# Polarshield_v2_1.net
KiCad netlist of a schematic drawn in EAGLE
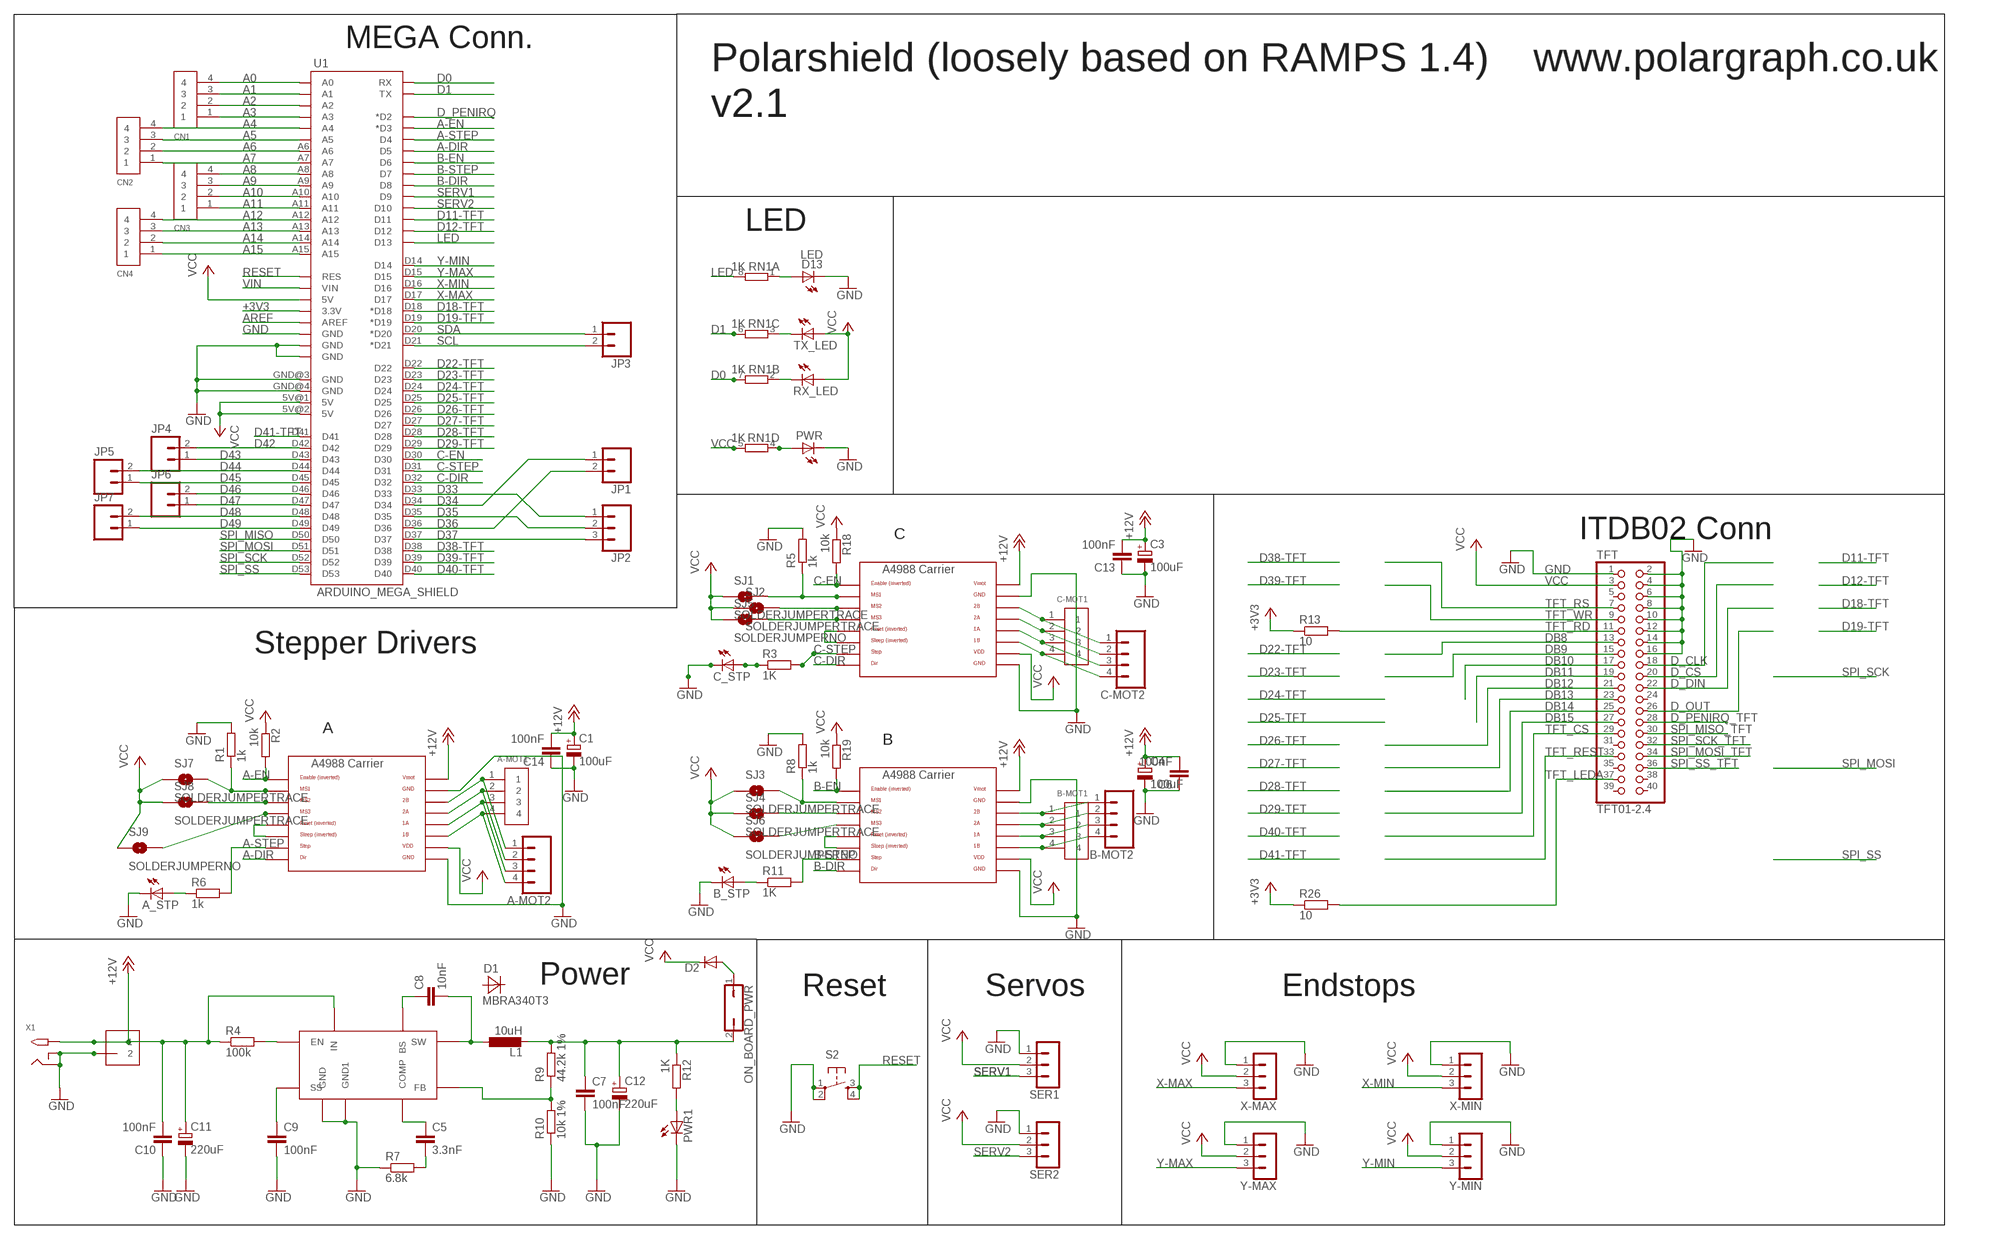
[diagram p0: schematic, sheet 1, part 1 of 2]
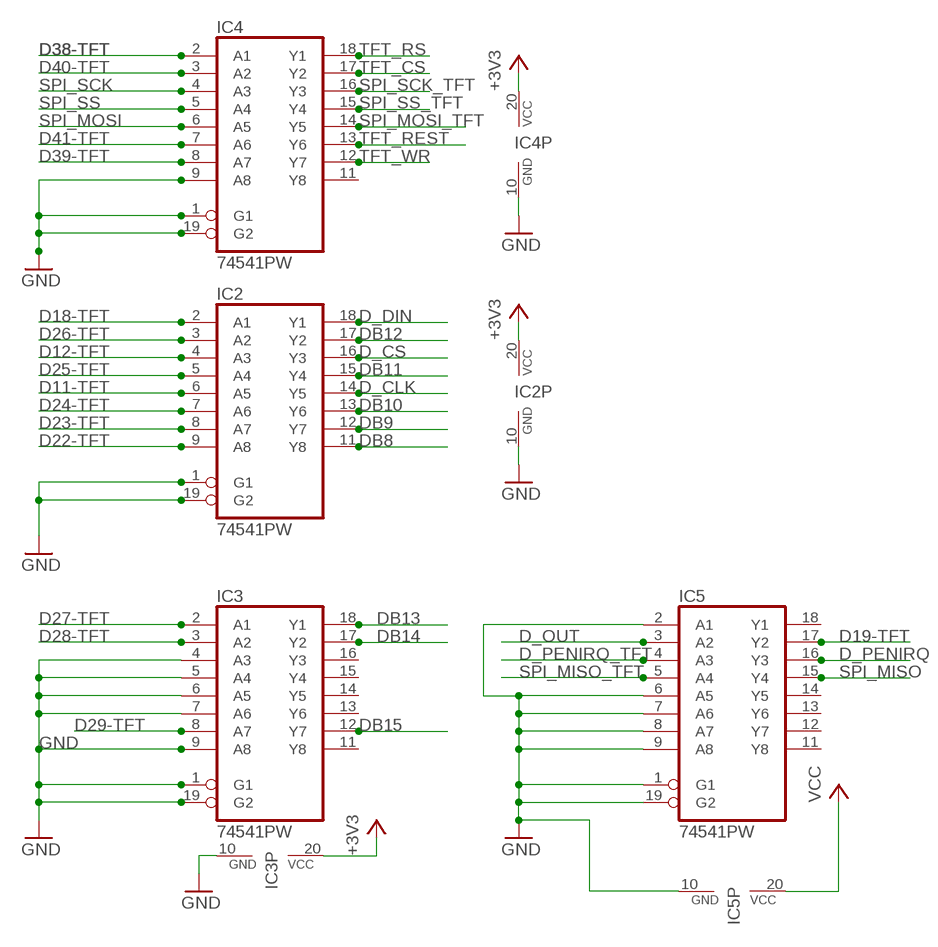
[diagram p1: schematic, sheet 1, part 2 of 2]

(export (version "E")
  (design (tool "Eeschema 10.0.6"))
  (components
    (comp (ref "A-MOT1")
      (value "1X4-BIG")
      (footprint "eagle-import:1X04-BIG")
      (libsource (lib "eagle-import") (part "adafruit_1X4-BIG"))
    )
    (comp (ref "A-MOT2")
      (value "M04SCREW")
      (footprint "eagle-import:SCREWTERMINAL-3.5MM-4")
      (libsource (lib "eagle-import") (part "M04SCREW"))
    )
    (comp (ref "A_STP")
      (value "LEDCHIP-LED0805")
      (footprint "eagle-import:CHIP-LED0805")
      (libsource (lib "eagle-import") (part "LEDCHIP-LED0805"))
    )
    (comp (ref "B-MOT1")
      (value "1X4-BIG")
      (footprint "eagle-import:1X04-BIG")
      (libsource (lib "eagle-import") (part "adafruit_1X4-BIG"))
    )
    (comp (ref "B-MOT2")
      (value "M04SCREW")
      (footprint "eagle-import:SCREWTERMINAL-3.5MM-4")
      (libsource (lib "eagle-import") (part "M04SCREW"))
    )
    (comp (ref "B_STP")
      (value "LEDCHIP-LED0805")
      (footprint "eagle-import:CHIP-LED0805")
      (libsource (lib "eagle-import") (part "LEDCHIP-LED0805"))
    )
    (comp (ref "C-MOT1")
      (value "1X4-BIG")
      (footprint "eagle-import:1X04-BIG")
      (libsource (lib "eagle-import") (part "adafruit_1X4-BIG"))
    )
    (comp (ref "C-MOT2")
      (value "M04SCREW")
      (footprint "eagle-import:SCREWTERMINAL-3.5MM-4")
      (libsource (lib "eagle-import") (part "M04SCREW"))
    )
    (comp (ref "C1")
      (value "100uF")
      (footprint "eagle-import:153CLV-0605")
      (libsource (lib "eagle-import") (part "CPOL-EU153CLV-0605"))
    )
    (comp (ref "C3")
      (value "100uF")
      (footprint "eagle-import:153CLV-0605")
      (libsource (lib "eagle-import") (part "CPOL-EU153CLV-0605"))
    )
    (comp (ref "C4")
      (value "100uF")
      (footprint "eagle-import:153CLV-0605")
      (libsource (lib "eagle-import") (part "CPOL-EU153CLV-0605"))
    )
    (comp (ref "C5")
      (value "3.3nF")
      (footprint "eagle-import:C0805K")
      (libsource (lib "eagle-import") (part "C-EUC0805K"))
    )
    (comp (ref "C6")
      (value "100nF")
      (footprint "eagle-import:C0805")
      (libsource (lib "eagle-import") (part "C-EUC0805"))
    )
    (comp (ref "C7")
      (value "100nF")
      (footprint "eagle-import:C0805K")
      (libsource (lib "eagle-import") (part "C-EUC0805K"))
    )
    (comp (ref "C8")
      (value "10nF")
      (footprint "eagle-import:C0805K")
      (libsource (lib "eagle-import") (part "C-EUC0805K"))
    )
    (comp (ref "C9")
      (value "100nF")
      (footprint "eagle-import:C0805K")
      (libsource (lib "eagle-import") (part "C-EUC0805K"))
    )
    (comp (ref "C10")
      (value "100nF")
      (footprint "eagle-import:C0805K")
      (libsource (lib "eagle-import") (part "C-EUC0805K"))
    )
    (comp (ref "C11")
      (value "220uF")
      (footprint "eagle-import:153CLV-0807")
      (libsource (lib "eagle-import") (part "resistor_CPOL-EU153CLV-0807"))
    )
    (comp (ref "C12")
      (value "220uF")
      (footprint "eagle-import:153CLV-0807")
      (libsource (lib "eagle-import") (part "resistor_CPOL-EU153CLV-0807"))
    )
    (comp (ref "C13")
      (value "100nF")
      (footprint "eagle-import:C0805")
      (libsource (lib "eagle-import") (part "C-EUC0805"))
    )
    (comp (ref "C14")
      (value "100nF")
      (footprint "eagle-import:C0805")
      (libsource (lib "eagle-import") (part "C-EUC0805"))
    )
    (comp (ref "CN1")
      (value "1X4-CLEANBIG")
      (footprint "eagle-import:1X04-CLEANBIG")
      (libsource (lib "eagle-import") (part "1X4-CLEANBIG"))
    )
    (comp (ref "CN2")
      (value "1X4-CLEANBIG")
      (footprint "eagle-import:1X04-CLEANBIG")
      (libsource (lib "eagle-import") (part "1X4-CLEANBIG"))
    )
    (comp (ref "CN3")
      (value "1X4-CLEANBIG")
      (footprint "eagle-import:1X04-CLEANBIG")
      (libsource (lib "eagle-import") (part "1X4-CLEANBIG"))
    )
    (comp (ref "CN4")
      (value "1X4-CLEANBIG")
      (footprint "eagle-import:1X04-CLEANBIG")
      (libsource (lib "eagle-import") (part "1X4-CLEANBIG"))
    )
    (comp (ref "C_STP")
      (value "LEDCHIP-LED0805")
      (footprint "eagle-import:CHIP-LED0805")
      (libsource (lib "eagle-import") (part "LEDCHIP-LED0805"))
    )
    (comp (ref "D1")
      (value "MBRA340T3")
      (footprint "eagle-import:SMA")
      (libsource (lib "eagle-import") (part "MBRA340T3"))
    )
    (comp (ref "D2")
      (value "DIODE-DO214BA")
      (footprint "eagle-import:DO214BA")
      (libsource (lib "eagle-import") (part "DIODE-DO214BA"))
    )
    (comp (ref "D13")
      (value "LED")
      (footprint "eagle-import:CHIP-LED0805")
      (libsource (lib "eagle-import") (part "LEDCHIP-LED0805"))
    )
    (comp (ref "IC1")
      (value "MP2307")
      (footprint "eagle-import:SOIC8")
      (libsource (lib "eagle-import") (part "MP2307"))
    )
    (comp (ref "IC2")
      (value "74541PW")
      (footprint "eagle-import:TSSOP20")
      (libsource (lib "eagle-import") (part "74541PW"))
    )
    (comp (ref "IC3")
      (value "74541PW")
      (footprint "eagle-import:TSSOP20")
      (libsource (lib "eagle-import") (part "74541PW"))
    )
    (comp (ref "IC4")
      (value "74541PW")
      (footprint "eagle-import:TSSOP20")
      (libsource (lib "eagle-import") (part "74541PW"))
    )
    (comp (ref "IC5")
      (value "74541PW")
      (footprint "eagle-import:TSSOP20")
      (libsource (lib "eagle-import") (part "74541PW"))
    )
    (comp (ref "J1")
      (value "1X2-3.5MM")
      (footprint "eagle-import:1X2-3.5MM")
      (libsource (lib "eagle-import") (part "1X2-3.5MM"))
    )
    (comp (ref "JP1")
      (value "M02POGO_PIN_HOLES_ONLY")
      (footprint "eagle-import:1X02_PP_HOLES_ONLY")
      (libsource (lib "eagle-import") (part "M02POGO_PIN_HOLES_ONLY"))
    )
    (comp (ref "JP2")
      (value "M03POGO_PIN_HOLES_ONLY")
      (footprint "eagle-import:1X03_PP_HOLES_ONLY")
      (libsource (lib "eagle-import") (part "M03POGO_PIN_HOLES_ONLY"))
    )
    (comp (ref "JP3")
      (value "M02POGO_PIN_HOLES_ONLY")
      (footprint "eagle-import:1X02_PP_HOLES_ONLY")
      (libsource (lib "eagle-import") (part "M02POGO_PIN_HOLES_ONLY"))
    )
    (comp (ref "JP4")
      (value "M02POGO_PIN_HOLES_ONLY")
      (footprint "eagle-import:1X02_PP_HOLES_ONLY")
      (libsource (lib "eagle-import") (part "M02POGO_PIN_HOLES_ONLY"))
    )
    (comp (ref "JP5")
      (value "M02POGO_PIN_HOLES_ONLY")
      (footprint "eagle-import:1X02_PP_HOLES_ONLY")
      (libsource (lib "eagle-import") (part "M02POGO_PIN_HOLES_ONLY"))
    )
    (comp (ref "JP6")
      (value "M02POGO_PIN_HOLES_ONLY")
      (footprint "eagle-import:1X02_PP_HOLES_ONLY")
      (libsource (lib "eagle-import") (part "M02POGO_PIN_HOLES_ONLY"))
    )
    (comp (ref "JP7")
      (value "M02POGO_PIN_HOLES_ONLY")
      (footprint "eagle-import:1X02_PP_HOLES_ONLY")
      (libsource (lib "eagle-import") (part "M02POGO_PIN_HOLES_ONLY"))
    )
    (comp (ref "L1")
      (value "10uH")
      (footprint "eagle-import:PIS2816")
      (libsource (lib "eagle-import") (part "L-EUPIS2816"))
    )
    (comp (ref "ON_BOARD_PWR")
      (value "JP1Q")
      (footprint "eagle-import:JP1")
      (libsource (lib "eagle-import") (part "JP1Q"))
    )
    (comp (ref "PWR")
      (value "LEDCHIP-LED0805")
      (footprint "eagle-import:CHIP-LED0805")
      (libsource (lib "eagle-import") (part "LEDCHIP-LED0805"))
    )
    (comp (ref "PWR1")
      (value "LEDCHIP-LED0805")
      (footprint "eagle-import:CHIP-LED0805")
      (libsource (lib "eagle-import") (part "LEDCHIP-LED0805"))
    )
    (comp (ref "R1")
      (value "1k")
      (footprint "eagle-import:R0805")
      (libsource (lib "eagle-import") (part "R-EU_R0805"))
    )
    (comp (ref "R2")
      (value "10k")
      (footprint "eagle-import:R0805")
      (libsource (lib "eagle-import") (part "R-EU_R0805"))
    )
    (comp (ref "R3")
      (value "1K")
      (footprint "eagle-import:R0805")
      (libsource (lib "eagle-import") (part "R-EU_R0805"))
    )
    (comp (ref "R4")
      (value "100k")
      (footprint "eagle-import:R0805")
      (libsource (lib "eagle-import") (part "resistor_R-EU_R0805"))
    )
    (comp (ref "R5")
      (value "1k")
      (footprint "eagle-import:R0805")
      (libsource (lib "eagle-import") (part "R-EU_R0805"))
    )
    (comp (ref "R6")
      (value "1k")
      (footprint "eagle-import:R0805")
      (libsource (lib "eagle-import") (part "R-EU_R0805"))
    )
    (comp (ref "R7")
      (value "6.8k")
      (footprint "eagle-import:R0805")
      (libsource (lib "eagle-import") (part "resistor_R-EU_R0805"))
    )
    (comp (ref "R8")
      (value "1k")
      (footprint "eagle-import:R0805")
      (libsource (lib "eagle-import") (part "R-EU_R0805"))
    )
    (comp (ref "R9")
      (value "44.2k 1%")
      (footprint "eagle-import:R0805")
      (libsource (lib "eagle-import") (part "resistor_R-EU_R0805"))
    )
    (comp (ref "R10")
      (value "10k 1%")
      (footprint "eagle-import:R0805")
      (libsource (lib "eagle-import") (part "resistor_R-EU_R0805"))
    )
    (comp (ref "R11")
      (value "1K")
      (footprint "eagle-import:R0805")
      (libsource (lib "eagle-import") (part "R-EU_R0805"))
    )
    (comp (ref "R12")
      (value "1K")
      (footprint "eagle-import:R0805")
      (libsource (lib "eagle-import") (part "R-EU_R0805"))
    )
    (comp (ref "R13")
      (value "10")
      (footprint "eagle-import:R0805")
      (libsource (lib "eagle-import") (part "resistor_R-EU_R0805"))
    )
    (comp (ref "R18")
      (value "10k")
      (footprint "eagle-import:R0805")
      (libsource (lib "eagle-import") (part "R-EU_R0805"))
    )
    (comp (ref "R19")
      (value "10k")
      (footprint "eagle-import:R0805")
      (libsource (lib "eagle-import") (part "R-EU_R0805"))
    )
    (comp (ref "R26")
      (value "10")
      (footprint "eagle-import:R0805")
      (libsource (lib "eagle-import") (part "resistor_R-EU_R0805"))
    )
    (comp (ref "RN1")
      (value "1K")
      (footprint "eagle-import:EXBS8V")
      (libsource (lib "eagle-import") (part "4R-NEXBS8V"))
    )
    (comp (ref "RX_LED")
      (value "LEDCHIP-LED0805")
      (footprint "eagle-import:CHIP-LED0805")
      (libsource (lib "eagle-import") (part "LEDCHIP-LED0805"))
    )
    (comp (ref "S2")
      (value "TAC_SWITCHPTH")
      (footprint "eagle-import:TACTILE-PTH")
      (libsource (lib "eagle-import") (part "TAC_SWITCHPTH"))
    )
    (comp (ref "SER1")
      (value "3PIN-HEADER")
      (footprint "eagle-import:3PIN-HEADER")
      (libsource (lib "eagle-import") (part "3PIN-HEADER"))
    )
    (comp (ref "SER2")
      (value "3PIN-HEADER")
      (footprint "eagle-import:3PIN-HEADER")
      (libsource (lib "eagle-import") (part "3PIN-HEADER"))
    )
    (comp (ref "SJ1")
      (value "SOLDERJUMPERTRACE")
      (footprint "eagle-import:SJ_2S-TRACE")
      (libsource (lib "eagle-import") (part "SOLDERJUMPERTRACE"))
    )
    (comp (ref "SJ2")
      (value "SOLDERJUMPERTRACE")
      (footprint "eagle-import:SJ_2S-TRACE")
      (libsource (lib "eagle-import") (part "SOLDERJUMPERTRACE"))
    )
    (comp (ref "SJ3")
      (value "SOLDERJUMPERTRACE")
      (footprint "eagle-import:SJ_2S-TRACE")
      (libsource (lib "eagle-import") (part "SOLDERJUMPERTRACE"))
    )
    (comp (ref "SJ4")
      (value "SOLDERJUMPERTRACE")
      (footprint "eagle-import:SJ_2S-TRACE")
      (libsource (lib "eagle-import") (part "SOLDERJUMPERTRACE"))
    )
    (comp (ref "SJ5")
      (value "SOLDERJUMPERNO")
      (footprint "eagle-import:SJ_2S-NO")
      (libsource (lib "eagle-import") (part "SOLDERJUMPERNO"))
    )
    (comp (ref "SJ6")
      (value "SOLDERJUMPERNO")
      (footprint "eagle-import:SJ_2S-NO")
      (libsource (lib "eagle-import") (part "SOLDERJUMPERNO"))
    )
    (comp (ref "SJ7")
      (value "SOLDERJUMPERTRACE")
      (footprint "eagle-import:SJ_2S-TRACE")
      (libsource (lib "eagle-import") (part "SOLDERJUMPERTRACE"))
    )
    (comp (ref "SJ8")
      (value "SOLDERJUMPERTRACE")
      (footprint "eagle-import:SJ_2S-TRACE")
      (libsource (lib "eagle-import") (part "SOLDERJUMPERTRACE"))
    )
    (comp (ref "SJ9")
      (value "SOLDERJUMPERNO")
      (footprint "eagle-import:SJ_2S-NO")
      (libsource (lib "eagle-import") (part "SOLDERJUMPERNO"))
    )
    (comp (ref "TFT")
      (value "TFT01-2.4")
      (footprint "eagle-import:TFT01-2.4")
      (libsource (lib "eagle-import") (part "TFT01-2.4"))
    )
    (comp (ref "TX_LED")
      (value "LEDCHIP-LED0805")
      (footprint "eagle-import:CHIP-LED0805")
      (libsource (lib "eagle-import") (part "LEDCHIP-LED0805"))
    )
    (comp (ref "U$1")
      (value "A4988BREAKOUT")
      (footprint "eagle-import:A4988BREAKOUT")
      (libsource (lib "eagle-import") (part "A4988BREAKOUT"))
    )
    (comp (ref "U$6")
      (value "A4988BREAKOUT")
      (footprint "eagle-import:A4988BREAKOUT")
      (libsource (lib "eagle-import") (part "A4988BREAKOUT"))
    )
    (comp (ref "U$7")
      (value "A4988BREAKOUT")
      (footprint "eagle-import:A4988BREAKOUT")
      (libsource (lib "eagle-import") (part "A4988BREAKOUT"))
    )
    (comp (ref "U1")
      (value "ARDUINO_MEGA_SHIELD")
      (footprint "eagle-import:ARDUINO_MEGA_SHIELD")
      (libsource (lib "eagle-import") (part "ARDUINO_MEGA_SHIELD"))
    )
    (comp (ref "X-MAX")
      (value "3PIN-HEADER")
      (footprint "eagle-import:3PIN-HEADER")
      (libsource (lib "eagle-import") (part "3PIN-HEADER"))
    )
    (comp (ref "X-MIN")
      (value "3PIN-HEADER")
      (footprint "eagle-import:3PIN-HEADER")
      (libsource (lib "eagle-import") (part "3PIN-HEADER"))
    )
    (comp (ref "X1")
      (value "2.1MMJACKTHM")
      (footprint "eagle-import:PJ-102A")
      (libsource (lib "eagle-import") (part "2.1MMJACKTHM"))
    )
    (comp (ref "Y-MAX")
      (value "3PIN-HEADER")
      (footprint "eagle-import:3PIN-HEADER")
      (libsource (lib "eagle-import") (part "3PIN-HEADER"))
    )
    (comp (ref "Y-MIN")
      (value "3PIN-HEADER")
      (footprint "eagle-import:3PIN-HEADER")
      (libsource (lib "eagle-import") (part "3PIN-HEADER"))
    )
  )
  (nets
    (net (code "1") (name "+3V3") (class "Default")
      (node (ref "IC2") (pin "20") (pinfunction "VCC_20") (pintype "power_in"))
      (node (ref "IC3") (pin "20") (pinfunction "VCC_20") (pintype "power_in"))
      (node (ref "IC4") (pin "20") (pinfunction "VCC_20") (pintype "power_in"))
      (node (ref "R13") (pin "1") (pinfunction "1_1") (pintype "passive"))
      (node (ref "R26") (pin "1") (pinfunction "1_1") (pintype "passive"))
      (node (ref "U1") (pin "3.3V") (pinfunction "3.3V_3.3V") (pintype "bidirectional"))
    )
    (net (code "2") (name "+12V") (class "Default")
      (node (ref "C1") (pin "+") (pinfunction "+_+") (pintype "passive"))
      (node (ref "C10") (pin "2") (pinfunction "2_2") (pintype "passive"))
      (node (ref "C11") (pin "+") (pinfunction "+_+") (pintype "passive"))
      (node (ref "C13") (pin "2") (pinfunction "2_2") (pintype "passive"))
      (node (ref "C14") (pin "2") (pinfunction "2_2") (pintype "passive"))
      (node (ref "C3") (pin "+") (pinfunction "+_+") (pintype "passive"))
      (node (ref "C4") (pin "+") (pinfunction "+_+") (pintype "passive"))
      (node (ref "C6") (pin "2") (pinfunction "2_2") (pintype "passive"))
      (node (ref "IC1") (pin "IN") (pinfunction "IN_IN") (pintype "bidirectional"))
      (node (ref "J1") (pin "1") (pinfunction "1_1") (pintype "passive"))
      (node (ref "R4") (pin "1") (pinfunction "1_1") (pintype "passive"))
      (node (ref "U$1") (pin "VMOT") (pinfunction "VMOT_VMOT") (pintype "power_in"))
      (node (ref "U$6") (pin "VMOT") (pinfunction "VMOT_VMOT") (pintype "power_in"))
      (node (ref "U$7") (pin "VMOT") (pinfunction "VMOT_VMOT") (pintype "power_in"))
      (node (ref "X1") (pin "TIP") (pinfunction "TIP_TIP") (pintype "bidirectional"))
    )
    (net (code "3") (name "/A-DIR") (class "Default")
      (node (ref "U$1") (pin "DIR") (pinfunction "DIR_DIR") (pintype "input"))
      (node (ref "U1") (pin "D5") (pinfunction "D5_D5") (pintype "bidirectional"))
    )
    (net (code "4") (name "/A-EN") (class "Default")
      (node (ref "R2") (pin "2") (pinfunction "2_2") (pintype "passive"))
      (node (ref "U$1") (pin "EN") (pinfunction "EN_EN") (pintype "input"))
      (node (ref "U1") (pin "D3") (pinfunction "*D3_D3") (pintype "bidirectional"))
    )
    (net (code "5") (name "/A-STEP") (class "Default")
      (node (ref "R6") (pin "2") (pinfunction "2_2") (pintype "passive"))
      (node (ref "U$1") (pin "STEP") (pinfunction "STEP_STEP") (pintype "input"))
      (node (ref "U1") (pin "D4") (pinfunction "D4_D4") (pintype "bidirectional"))
    )
    (net (code "6") (name "/A0") (class "Default")
      (node (ref "CN1") (pin "4") (pinfunction "4_4") (pintype "bidirectional"))
      (node (ref "U1") (pin "A0") (pinfunction "A0_A0") (pintype "bidirectional"))
    )
    (net (code "7") (name "/A1") (class "Default")
      (node (ref "CN1") (pin "3") (pinfunction "3_3") (pintype "bidirectional"))
      (node (ref "U1") (pin "A1") (pinfunction "A1_A1") (pintype "bidirectional"))
    )
    (net (code "8") (name "/A2") (class "Default")
      (node (ref "CN1") (pin "2") (pinfunction "2_2") (pintype "bidirectional"))
      (node (ref "U1") (pin "A2") (pinfunction "A2_A2") (pintype "bidirectional"))
    )
    (net (code "9") (name "/A3") (class "Default")
      (node (ref "CN1") (pin "1") (pinfunction "1_1") (pintype "bidirectional"))
      (node (ref "U1") (pin "A3") (pinfunction "A3_A3") (pintype "bidirectional"))
    )
    (net (code "10") (name "/A4") (class "Default")
      (node (ref "CN2") (pin "4") (pinfunction "4_4") (pintype "bidirectional"))
      (node (ref "U1") (pin "A4") (pinfunction "A4_A4") (pintype "bidirectional"))
    )
    (net (code "11") (name "/A5") (class "Default")
      (node (ref "CN2") (pin "3") (pinfunction "3_3") (pintype "bidirectional"))
      (node (ref "U1") (pin "A5") (pinfunction "A5_A5") (pintype "bidirectional"))
    )
    (net (code "12") (name "/A6") (class "Default")
      (node (ref "CN2") (pin "2") (pinfunction "2_2") (pintype "bidirectional"))
      (node (ref "U1") (pin "A6") (pinfunction "A6_A6") (pintype "bidirectional"))
    )
    (net (code "13") (name "/A7") (class "Default")
      (node (ref "CN2") (pin "1") (pinfunction "1_1") (pintype "bidirectional"))
      (node (ref "U1") (pin "A7") (pinfunction "A7_A7") (pintype "bidirectional"))
    )
    (net (code "14") (name "/A8") (class "Default")
      (node (ref "CN3") (pin "4") (pinfunction "4_4") (pintype "bidirectional"))
      (node (ref "U1") (pin "A8") (pinfunction "A8_A8") (pintype "bidirectional"))
    )
    (net (code "15") (name "/A9") (class "Default")
      (node (ref "CN3") (pin "3") (pinfunction "3_3") (pintype "bidirectional"))
      (node (ref "U1") (pin "A9") (pinfunction "A9_A9") (pintype "bidirectional"))
    )
    (net (code "16") (name "/A10") (class "Default")
      (node (ref "CN3") (pin "2") (pinfunction "2_2") (pintype "bidirectional"))
      (node (ref "U1") (pin "A10") (pinfunction "A10_A10") (pintype "bidirectional"))
    )
    (net (code "17") (name "/A11") (class "Default")
      (node (ref "CN3") (pin "1") (pinfunction "1_1") (pintype "bidirectional"))
      (node (ref "U1") (pin "A11") (pinfunction "A11_A11") (pintype "bidirectional"))
    )
    (net (code "18") (name "/A12") (class "Default")
      (node (ref "CN4") (pin "4") (pinfunction "4_4") (pintype "bidirectional"))
      (node (ref "U1") (pin "A12") (pinfunction "A12_A12") (pintype "bidirectional"))
    )
    (net (code "19") (name "/A13") (class "Default")
      (node (ref "CN4") (pin "3") (pinfunction "3_3") (pintype "bidirectional"))
      (node (ref "U1") (pin "A13") (pinfunction "A13_A13") (pintype "bidirectional"))
    )
    (net (code "20") (name "/A14") (class "Default")
      (node (ref "CN4") (pin "2") (pinfunction "2_2") (pintype "bidirectional"))
      (node (ref "U1") (pin "A14") (pinfunction "A14_A14") (pintype "bidirectional"))
    )
    (net (code "21") (name "/A15") (class "Default")
      (node (ref "CN4") (pin "1") (pinfunction "1_1") (pintype "bidirectional"))
      (node (ref "U1") (pin "A15") (pinfunction "A15_A15") (pintype "bidirectional"))
    )
    (net (code "22") (name "/AREF") (class "Default")
      (node (ref "U1") (pin "AREF") (pinfunction "AREF_AREF") (pintype "bidirectional"))
    )
    (net (code "23") (name "/B-DIR") (class "Default")
      (node (ref "U$7") (pin "DIR") (pinfunction "DIR_DIR") (pintype "input"))
      (node (ref "U1") (pin "D8") (pinfunction "D8_D8") (pintype "bidirectional"))
    )
    (net (code "24") (name "/B-EN") (class "Default")
      (node (ref "R19") (pin "2") (pinfunction "2_2") (pintype "passive"))
      (node (ref "U$7") (pin "EN") (pinfunction "EN_EN") (pintype "input"))
      (node (ref "U1") (pin "D6") (pinfunction "D6_D6") (pintype "bidirectional"))
    )
    (net (code "25") (name "/B-STEP") (class "Default")
      (node (ref "R11") (pin "2") (pinfunction "2_2") (pintype "passive"))
      (node (ref "U$7") (pin "STEP") (pinfunction "STEP_STEP") (pintype "input"))
      (node (ref "U1") (pin "D7") (pinfunction "D7_D7") (pintype "bidirectional"))
    )
    (net (code "26") (name "/C-DIR") (class "Default")
      (node (ref "U$6") (pin "DIR") (pinfunction "DIR_DIR") (pintype "input"))
      (node (ref "U1") (pin "D32") (pinfunction "D32_D32") (pintype "bidirectional"))
    )
    (net (code "27") (name "/C-EN") (class "Default")
      (node (ref "R18") (pin "2") (pinfunction "2_2") (pintype "passive"))
      (node (ref "U$6") (pin "EN") (pinfunction "EN_EN") (pintype "input"))
      (node (ref "U1") (pin "D30") (pinfunction "D30_D30") (pintype "bidirectional"))
    )
    (net (code "28") (name "/C-STEP") (class "Default")
      (node (ref "R3") (pin "2") (pinfunction "2_2") (pintype "passive"))
      (node (ref "U$6") (pin "STEP") (pinfunction "STEP_STEP") (pintype "input"))
      (node (ref "U1") (pin "D31") (pinfunction "D31_D31") (pintype "bidirectional"))
    )
    (net (code "29") (name "/D0") (class "Default")
      (node (ref "RN1") (pin "7") (pinfunction "2_7") (pintype "passive"))
      (node (ref "U1") (pin "RX") (pinfunction "RX_RX") (pintype "bidirectional"))
    )
    (net (code "30") (name "/D1") (class "Default")
      (node (ref "RN1") (pin "6") (pinfunction "2_6") (pintype "passive"))
      (node (ref "U1") (pin "TX") (pinfunction "TX_TX") (pintype "bidirectional"))
    )
    (net (code "31") (name "/D11-TFT") (class "Default")
      (node (ref "IC2") (pin "6") (pinfunction "A5_6") (pintype "input"))
      (node (ref "U1") (pin "D11") (pinfunction "D11_D11") (pintype "bidirectional"))
    )
    (net (code "32") (name "/D12-TFT") (class "Default")
      (node (ref "IC2") (pin "4") (pinfunction "A3_4") (pintype "input"))
      (node (ref "U1") (pin "D12") (pinfunction "D12_D12") (pintype "bidirectional"))
    )
    (net (code "33") (name "/D18-TFT") (class "Default")
      (node (ref "IC2") (pin "2") (pinfunction "A1_2") (pintype "input"))
      (node (ref "U1") (pin "D18") (pinfunction "*D18_D18") (pintype "bidirectional"))
    )
    (net (code "34") (name "/D19-TFT") (class "Default")
      (node (ref "IC5") (pin "17") (pinfunction "Y2_17") (pintype "tri_state"))
      (node (ref "U1") (pin "D19") (pinfunction "*D19_D19") (pintype "bidirectional"))
    )
    (net (code "35") (name "/D22-TFT") (class "Default")
      (node (ref "IC2") (pin "9") (pinfunction "A8_9") (pintype "input"))
      (node (ref "U1") (pin "D22") (pinfunction "D22_D22") (pintype "bidirectional"))
    )
    (net (code "36") (name "/D23-TFT") (class "Default")
      (node (ref "IC2") (pin "8") (pinfunction "A7_8") (pintype "input"))
      (node (ref "U1") (pin "D23") (pinfunction "D23_D23") (pintype "bidirectional"))
    )
    (net (code "37") (name "/D24-TFT") (class "Default")
      (node (ref "IC2") (pin "7") (pinfunction "A6_7") (pintype "input"))
      (node (ref "U1") (pin "D24") (pinfunction "D24_D24") (pintype "bidirectional"))
    )
    (net (code "38") (name "/D25-TFT") (class "Default")
      (node (ref "IC2") (pin "5") (pinfunction "A4_5") (pintype "input"))
      (node (ref "U1") (pin "D25") (pinfunction "D25_D25") (pintype "bidirectional"))
    )
    (net (code "39") (name "/D26-TFT") (class "Default")
      (node (ref "IC2") (pin "3") (pinfunction "A2_3") (pintype "input"))
      (node (ref "U1") (pin "D26") (pinfunction "D26_D26") (pintype "bidirectional"))
    )
    (net (code "40") (name "/D27-TFT") (class "Default")
      (node (ref "IC3") (pin "2") (pinfunction "A1_2") (pintype "input"))
      (node (ref "U1") (pin "D27") (pinfunction "D27_D27") (pintype "bidirectional"))
    )
    (net (code "41") (name "/D28-TFT") (class "Default")
      (node (ref "IC3") (pin "3") (pinfunction "A2_3") (pintype "input"))
      (node (ref "U1") (pin "D28") (pinfunction "D28_D28") (pintype "bidirectional"))
    )
    (net (code "42") (name "/D29-TFT") (class "Default")
      (node (ref "IC3") (pin "8") (pinfunction "A7_8") (pintype "input"))
      (node (ref "U1") (pin "D29") (pinfunction "D29_D29") (pintype "bidirectional"))
    )
    (net (code "43") (name "/D33") (class "Default")
      (node (ref "JP2") (pin "1") (pinfunction "1_1") (pintype "passive"))
      (node (ref "U1") (pin "D33") (pinfunction "D33_D33") (pintype "bidirectional"))
    )
    (net (code "44") (name "/D34") (class "Default")
      (node (ref "JP1") (pin "1") (pinfunction "1_1") (pintype "passive"))
      (node (ref "U1") (pin "D34") (pinfunction "D34_D34") (pintype "bidirectional"))
    )
    (net (code "45") (name "/D35") (class "Default")
      (node (ref "JP2") (pin "2") (pinfunction "2_2") (pintype "passive"))
      (node (ref "U1") (pin "D35") (pinfunction "D35_D35") (pintype "bidirectional"))
    )
    (net (code "46") (name "/D36") (class "Default")
      (node (ref "JP1") (pin "2") (pinfunction "2_2") (pintype "passive"))
      (node (ref "U1") (pin "D36") (pinfunction "D36_D36") (pintype "bidirectional"))
    )
    (net (code "47") (name "/D37") (class "Default")
      (node (ref "JP2") (pin "3") (pinfunction "3_3") (pintype "passive"))
      (node (ref "U1") (pin "D37") (pinfunction "D37_D37") (pintype "bidirectional"))
    )
    (net (code "48") (name "/D38-TFT") (class "Default")
      (node (ref "IC4") (pin "2") (pinfunction "A1_2") (pintype "input"))
      (node (ref "U1") (pin "D38") (pinfunction "D38_D38") (pintype "bidirectional"))
    )
    (net (code "49") (name "/D39-TFT") (class "Default")
      (node (ref "IC4") (pin "8") (pinfunction "A7_8") (pintype "input"))
      (node (ref "U1") (pin "D39") (pinfunction "D39_D39") (pintype "bidirectional"))
    )
    (net (code "50") (name "/D40-TFT") (class "Default")
      (node (ref "IC4") (pin "3") (pinfunction "A2_3") (pintype "input"))
      (node (ref "U1") (pin "D40") (pinfunction "D40_D40") (pintype "bidirectional"))
    )
    (net (code "51") (name "/D41-TFT") (class "Default")
      (node (ref "IC4") (pin "7") (pinfunction "A6_7") (pintype "input"))
      (node (ref "U1") (pin "D41") (pinfunction "D41_D41") (pintype "bidirectional"))
    )
    (net (code "52") (name "/D42") (class "Default")
      (node (ref "JP4") (pin "2") (pinfunction "2_2") (pintype "passive"))
      (node (ref "U1") (pin "D42") (pinfunction "D42_D42") (pintype "bidirectional"))
    )
    (net (code "53") (name "/D43") (class "Default")
      (node (ref "JP4") (pin "1") (pinfunction "1_1") (pintype "passive"))
      (node (ref "U1") (pin "D43") (pinfunction "D43_D43") (pintype "bidirectional"))
    )
    (net (code "54") (name "/D44") (class "Default")
      (node (ref "JP5") (pin "2") (pinfunction "2_2") (pintype "passive"))
      (node (ref "U1") (pin "D44") (pinfunction "D44_D44") (pintype "bidirectional"))
    )
    (net (code "55") (name "/D45") (class "Default")
      (node (ref "JP5") (pin "1") (pinfunction "1_1") (pintype "passive"))
      (node (ref "U1") (pin "D45") (pinfunction "D45_D45") (pintype "bidirectional"))
    )
    (net (code "56") (name "/D46") (class "Default")
      (node (ref "JP6") (pin "2") (pinfunction "2_2") (pintype "passive"))
      (node (ref "U1") (pin "D46") (pinfunction "D46_D46") (pintype "bidirectional"))
    )
    (net (code "57") (name "/D47") (class "Default")
      (node (ref "JP6") (pin "1") (pinfunction "1_1") (pintype "passive"))
      (node (ref "U1") (pin "D47") (pinfunction "D47_D47") (pintype "bidirectional"))
    )
    (net (code "58") (name "/D48") (class "Default")
      (node (ref "JP7") (pin "2") (pinfunction "2_2") (pintype "passive"))
      (node (ref "U1") (pin "D48") (pinfunction "D48_D48") (pintype "bidirectional"))
    )
    (net (code "59") (name "/D49") (class "Default")
      (node (ref "JP7") (pin "1") (pinfunction "1_1") (pintype "passive"))
      (node (ref "U1") (pin "D49") (pinfunction "D49_D49") (pintype "bidirectional"))
    )
    (net (code "60") (name "/DB8") (class "Default")
      (node (ref "IC2") (pin "11") (pinfunction "Y8_11") (pintype "tri_state"))
      (node (ref "TFT") (pin "13") (pinfunction "13_13") (pintype "passive"))
    )
    (net (code "61") (name "/DB9") (class "Default")
      (node (ref "IC2") (pin "12") (pinfunction "Y7_12") (pintype "tri_state"))
      (node (ref "TFT") (pin "15") (pinfunction "15_15") (pintype "passive"))
    )
    (net (code "62") (name "/DB10") (class "Default")
      (node (ref "IC2") (pin "13") (pinfunction "Y6_13") (pintype "tri_state"))
      (node (ref "TFT") (pin "17") (pinfunction "17_17") (pintype "passive"))
    )
    (net (code "63") (name "/DB11") (class "Default")
      (node (ref "IC2") (pin "15") (pinfunction "Y4_15") (pintype "tri_state"))
      (node (ref "TFT") (pin "19") (pinfunction "19_19") (pintype "passive"))
    )
    (net (code "64") (name "/DB12") (class "Default")
      (node (ref "IC2") (pin "17") (pinfunction "Y2_17") (pintype "tri_state"))
      (node (ref "TFT") (pin "21") (pinfunction "21_21") (pintype "passive"))
    )
    (net (code "65") (name "/DB13") (class "Default")
      (node (ref "IC3") (pin "18") (pinfunction "Y1_18") (pintype "tri_state"))
      (node (ref "TFT") (pin "23") (pinfunction "23_23") (pintype "passive"))
    )
    (net (code "66") (name "/DB14") (class "Default")
      (node (ref "IC3") (pin "17") (pinfunction "Y2_17") (pintype "tri_state"))
      (node (ref "TFT") (pin "25") (pinfunction "25_25") (pintype "passive"))
    )
    (net (code "67") (name "/DB15") (class "Default")
      (node (ref "IC3") (pin "12") (pinfunction "Y7_12") (pintype "tri_state"))
      (node (ref "TFT") (pin "27") (pinfunction "27_27") (pintype "passive"))
    )
    (net (code "68") (name "/D_CLK") (class "Default")
      (node (ref "IC2") (pin "14") (pinfunction "Y5_14") (pintype "tri_state"))
      (node (ref "TFT") (pin "18") (pinfunction "18_18") (pintype "passive"))
    )
    (net (code "69") (name "/D_CS") (class "Default")
      (node (ref "IC2") (pin "16") (pinfunction "Y3_16") (pintype "tri_state"))
      (node (ref "TFT") (pin "20") (pinfunction "20_20") (pintype "passive"))
    )
    (net (code "70") (name "/D_DIN") (class "Default")
      (node (ref "IC2") (pin "18") (pinfunction "Y1_18") (pintype "tri_state"))
      (node (ref "TFT") (pin "22") (pinfunction "22_22") (pintype "passive"))
    )
    (net (code "71") (name "/D_OUT") (class "Default")
      (node (ref "IC5") (pin "3") (pinfunction "A2_3") (pintype "input"))
      (node (ref "TFT") (pin "26") (pinfunction "26_26") (pintype "passive"))
    )
    (net (code "72") (name "/D_PENIRQ") (class "Default")
      (node (ref "IC5") (pin "16") (pinfunction "Y3_16") (pintype "tri_state"))
      (node (ref "U1") (pin "D2") (pinfunction "*D2_D2") (pintype "bidirectional"))
    )
    (net (code "73") (name "/D_PENIRQ_TFT") (class "Default")
      (node (ref "IC5") (pin "4") (pinfunction "A3_4") (pintype "input"))
      (node (ref "TFT") (pin "28") (pinfunction "28_28") (pintype "passive"))
    )
    (net (code "74") (name "/LED") (class "Default")
      (node (ref "RN1") (pin "8") (pinfunction "2_8") (pintype "passive"))
      (node (ref "U1") (pin "D13") (pinfunction "D13_D13") (pintype "bidirectional"))
    )
    (net (code "75") (name "/RESET") (class "Default")
      (node (ref "S2") (pin "3") (pinfunction "3_3") (pintype "passive"))
      (node (ref "S2") (pin "4") (pinfunction "4_4") (pintype "passive"))
      (node (ref "U1") (pin "RES") (pinfunction "RES_RES") (pintype "bidirectional"))
    )
    (net (code "76") (name "/SCL") (class "Default")
      (node (ref "JP3") (pin "2") (pinfunction "2_2") (pintype "passive"))
      (node (ref "U1") (pin "D21") (pinfunction "*D21_D21") (pintype "bidirectional"))
    )
    (net (code "77") (name "/SDA") (class "Default")
      (node (ref "JP3") (pin "1") (pinfunction "1_1") (pintype "passive"))
      (node (ref "U1") (pin "D20") (pinfunction "*D20_D20") (pintype "bidirectional"))
    )
    (net (code "78") (name "/SERV1") (class "Default")
      (node (ref "SER1") (pin "3") (pinfunction "3_3") (pintype "passive"))
      (node (ref "U1") (pin "D9") (pinfunction "D9_D9") (pintype "bidirectional"))
    )
    (net (code "79") (name "/SERV2") (class "Default")
      (node (ref "SER2") (pin "3") (pinfunction "3_3") (pintype "passive"))
      (node (ref "U1") (pin "D10") (pinfunction "D10_D10") (pintype "bidirectional"))
    )
    (net (code "80") (name "/SPI_MISO") (class "Default")
      (node (ref "IC5") (pin "15") (pinfunction "Y4_15") (pintype "tri_state"))
      (node (ref "U1") (pin "D50") (pinfunction "D50_D50") (pintype "bidirectional"))
    )
    (net (code "81") (name "/SPI_MISO_TFT") (class "Default")
      (node (ref "IC5") (pin "5") (pinfunction "A4_5") (pintype "input"))
      (node (ref "TFT") (pin "30") (pinfunction "30_30") (pintype "passive"))
    )
    (net (code "82") (name "/SPI_MOSI") (class "Default")
      (node (ref "IC4") (pin "6") (pinfunction "A5_6") (pintype "input"))
      (node (ref "U1") (pin "D51") (pinfunction "D51_D51") (pintype "bidirectional"))
    )
    (net (code "83") (name "/SPI_MOSI_TFT") (class "Default")
      (node (ref "IC4") (pin "14") (pinfunction "Y5_14") (pintype "tri_state"))
      (node (ref "TFT") (pin "34") (pinfunction "34_34") (pintype "passive"))
    )
    (net (code "84") (name "/SPI_SCK") (class "Default")
      (node (ref "IC4") (pin "4") (pinfunction "A3_4") (pintype "input"))
      (node (ref "U1") (pin "D52") (pinfunction "D52_D52") (pintype "bidirectional"))
    )
    (net (code "85") (name "/SPI_SCK_TFT") (class "Default")
      (node (ref "IC4") (pin "16") (pinfunction "Y3_16") (pintype "tri_state"))
      (node (ref "TFT") (pin "32") (pinfunction "32_32") (pintype "passive"))
    )
    (net (code "86") (name "/SPI_SS") (class "Default")
      (node (ref "IC4") (pin "5") (pinfunction "A4_5") (pintype "input"))
      (node (ref "U1") (pin "D53") (pinfunction "D53_D53") (pintype "bidirectional"))
    )
    (net (code "87") (name "/SPI_SS_TFT") (class "Default")
      (node (ref "IC4") (pin "15") (pinfunction "Y4_15") (pintype "tri_state"))
      (node (ref "TFT") (pin "36") (pinfunction "36_36") (pintype "passive"))
    )
    (net (code "88") (name "/TFT_CS") (class "Default")
      (node (ref "IC4") (pin "17") (pinfunction "Y2_17") (pintype "tri_state"))
      (node (ref "TFT") (pin "29") (pinfunction "29_29") (pintype "passive"))
    )
    (net (code "89") (name "/TFT_LEDA") (class "Default")
      (node (ref "R26") (pin "2") (pinfunction "2_2") (pintype "passive"))
      (node (ref "TFT") (pin "37") (pinfunction "37_37") (pintype "passive"))
    )
    (net (code "90") (name "/TFT_RD") (class "Default")
      (node (ref "R13") (pin "2") (pinfunction "2_2") (pintype "passive"))
      (node (ref "TFT") (pin "11") (pinfunction "11_11") (pintype "passive"))
    )
    (net (code "91") (name "/TFT_REST") (class "Default")
      (node (ref "IC4") (pin "13") (pinfunction "Y6_13") (pintype "tri_state"))
      (node (ref "TFT") (pin "33") (pinfunction "33_33") (pintype "passive"))
    )
    (net (code "92") (name "/TFT_RS") (class "Default")
      (node (ref "IC4") (pin "18") (pinfunction "Y1_18") (pintype "tri_state"))
      (node (ref "TFT") (pin "7") (pinfunction "7_7") (pintype "passive"))
    )
    (net (code "93") (name "/TFT_WR") (class "Default")
      (node (ref "IC4") (pin "12") (pinfunction "Y7_12") (pintype "tri_state"))
      (node (ref "TFT") (pin "9") (pinfunction "9_9") (pintype "passive"))
    )
    (net (code "94") (name "/VIN") (class "Default")
      (node (ref "U1") (pin "VIN") (pinfunction "VIN_VIN") (pintype "bidirectional"))
    )
    (net (code "95") (name "/X-MAX") (class "Default")
      (node (ref "U1") (pin "D17") (pinfunction "D17_D17") (pintype "bidirectional"))
      (node (ref "X-MAX") (pin "3") (pinfunction "3_3") (pintype "passive"))
    )
    (net (code "96") (name "/X-MIN") (class "Default")
      (node (ref "U1") (pin "D16") (pinfunction "D16_D16") (pintype "bidirectional"))
      (node (ref "X-MIN") (pin "3") (pinfunction "3_3") (pintype "passive"))
    )
    (net (code "97") (name "/Y-MAX") (class "Default")
      (node (ref "U1") (pin "D15") (pinfunction "D15_D15") (pintype "bidirectional"))
      (node (ref "Y-MAX") (pin "3") (pinfunction "3_3") (pintype "passive"))
    )
    (net (code "98") (name "/Y-MIN") (class "Default")
      (node (ref "U1") (pin "D14") (pinfunction "D14_D14") (pintype "bidirectional"))
      (node (ref "Y-MIN") (pin "3") (pinfunction "3_3") (pintype "passive"))
    )
    (net (code "99") (name "GND") (class "Default")
      (node (ref "A_STP") (pin "C") (pinfunction "C_C") (pintype "passive"))
      (node (ref "B_STP") (pin "C") (pinfunction "C_C") (pintype "passive"))
      (node (ref "C1") (pin "-") (pinfunction "-_-") (pintype "passive"))
      (node (ref "C10") (pin "1") (pinfunction "1_1") (pintype "passive"))
      (node (ref "C11") (pin "-") (pinfunction "-_-") (pintype "passive"))
      (node (ref "C12") (pin "-") (pinfunction "-_-") (pintype "passive"))
      (node (ref "C13") (pin "1") (pinfunction "1_1") (pintype "passive"))
      (node (ref "C14") (pin "1") (pinfunction "1_1") (pintype "passive"))
      (node (ref "C3") (pin "-") (pinfunction "-_-") (pintype "passive"))
      (node (ref "C4") (pin "-") (pinfunction "-_-") (pintype "passive"))
      (node (ref "C6") (pin "1") (pinfunction "1_1") (pintype "passive"))
      (node (ref "C7") (pin "2") (pinfunction "2_2") (pintype "passive"))
      (node (ref "C9") (pin "2") (pinfunction "2_2") (pintype "passive"))
      (node (ref "C_STP") (pin "C") (pinfunction "C_C") (pintype "passive"))
      (node (ref "D13") (pin "C") (pinfunction "C_C") (pintype "passive"))
      (node (ref "IC1") (pin "GND") (pinfunction "GND_GND") (pintype "bidirectional"))
      (node (ref "IC1") (pin "GND1") (pinfunction "GND1_GND1") (pintype "bidirectional"))
      (node (ref "IC2") (pin "1") (pinfunction "G1_1") (pintype "input"))
      (node (ref "IC2") (pin "10") (pinfunction "GND_10") (pintype "power_in"))
      (node (ref "IC2") (pin "19") (pinfunction "G2_19") (pintype "input"))
      (node (ref "IC3") (pin "1") (pinfunction "G1_1") (pintype "input"))
      (node (ref "IC3") (pin "10") (pinfunction "GND_10") (pintype "power_in"))
      (node (ref "IC3") (pin "19") (pinfunction "G2_19") (pintype "input"))
      (node (ref "IC3") (pin "4") (pinfunction "A3_4") (pintype "input"))
      (node (ref "IC3") (pin "5") (pinfunction "A4_5") (pintype "input"))
      (node (ref "IC3") (pin "6") (pinfunction "A5_6") (pintype "input"))
      (node (ref "IC3") (pin "7") (pinfunction "A6_7") (pintype "input"))
      (node (ref "IC3") (pin "9") (pinfunction "A8_9") (pintype "input"))
      (node (ref "IC4") (pin "1") (pinfunction "G1_1") (pintype "input"))
      (node (ref "IC4") (pin "10") (pinfunction "GND_10") (pintype "power_in"))
      (node (ref "IC4") (pin "19") (pinfunction "G2_19") (pintype "input"))
      (node (ref "IC4") (pin "9") (pinfunction "A8_9") (pintype "input"))
      (node (ref "IC5") (pin "1") (pinfunction "G1_1") (pintype "input"))
      (node (ref "IC5") (pin "10") (pinfunction "GND_10") (pintype "power_in"))
      (node (ref "IC5") (pin "19") (pinfunction "G2_19") (pintype "input"))
      (node (ref "IC5") (pin "2") (pinfunction "A1_2") (pintype "input"))
      (node (ref "IC5") (pin "6") (pinfunction "A5_6") (pintype "input"))
      (node (ref "IC5") (pin "7") (pinfunction "A6_7") (pintype "input"))
      (node (ref "IC5") (pin "8") (pinfunction "A7_8") (pintype "input"))
      (node (ref "IC5") (pin "9") (pinfunction "A8_9") (pintype "input"))
      (node (ref "J1") (pin "2") (pinfunction "2_2") (pintype "passive"))
      (node (ref "PWR") (pin "C") (pinfunction "C_C") (pintype "passive"))
      (node (ref "PWR1") (pin "C") (pinfunction "C_C") (pintype "passive"))
      (node (ref "R1") (pin "2") (pinfunction "2_2") (pintype "passive"))
      (node (ref "R10") (pin "1") (pinfunction "1_1") (pintype "passive"))
      (node (ref "R5") (pin "2") (pinfunction "2_2") (pintype "passive"))
      (node (ref "R7") (pin "1") (pinfunction "1_1") (pintype "passive"))
      (node (ref "R8") (pin "2") (pinfunction "2_2") (pintype "passive"))
      (node (ref "S2") (pin "1") (pinfunction "1_1") (pintype "passive"))
      (node (ref "S2") (pin "2") (pinfunction "2_2") (pintype "passive"))
      (node (ref "SER1") (pin "1") (pinfunction "1_1") (pintype "passive"))
      (node (ref "SER2") (pin "1") (pinfunction "1_1") (pintype "passive"))
      (node (ref "TFT") (pin "1") (pinfunction "1_1") (pintype "passive"))
      (node (ref "TFT") (pin "10") (pinfunction "10_10") (pintype "passive"))
      (node (ref "TFT") (pin "12") (pinfunction "12_12") (pintype "passive"))
      (node (ref "TFT") (pin "14") (pinfunction "14_14") (pintype "passive"))
      (node (ref "TFT") (pin "16") (pinfunction "16_16") (pintype "passive"))
      (node (ref "TFT") (pin "2") (pinfunction "2_2") (pintype "passive"))
      (node (ref "TFT") (pin "4") (pinfunction "4_4") (pintype "passive"))
      (node (ref "TFT") (pin "6") (pinfunction "6_6") (pintype "passive"))
      (node (ref "TFT") (pin "8") (pinfunction "8_8") (pintype "passive"))
      (node (ref "U$1") (pin "GND") (pinfunction "GND_GND") (pintype "power_in"))
      (node (ref "U$1") (pin "GND@0") (pinfunction "GND_GND@0") (pintype "power_in"))
      (node (ref "U$6") (pin "GND") (pinfunction "GND_GND") (pintype "power_in"))
      (node (ref "U$6") (pin "GND@0") (pinfunction "GND_GND@0") (pintype "power_in"))
      (node (ref "U$7") (pin "GND") (pinfunction "GND_GND") (pintype "power_in"))
      (node (ref "U$7") (pin "GND@0") (pinfunction "GND_GND@0") (pintype "power_in"))
      (node (ref "U1") (pin "GND@0") (pinfunction "GND_GND@0") (pintype "power_in"))
      (node (ref "U1") (pin "GND@1") (pinfunction "GND_GND@1") (pintype "power_in"))
      (node (ref "U1") (pin "GND@2") (pinfunction "GND_GND@2") (pintype "power_in"))
      (node (ref "U1") (pin "GND@3") (pinfunction "GND_GND@3") (pintype "power_in"))
      (node (ref "U1") (pin "GND@4") (pinfunction "GND_GND@4") (pintype "power_in"))
      (node (ref "X-MAX") (pin "1") (pinfunction "1_1") (pintype "passive"))
      (node (ref "X-MIN") (pin "1") (pinfunction "1_1") (pintype "passive"))
      (node (ref "X1") (pin "RING") (pinfunction "RING_RING") (pintype "bidirectional"))
      (node (ref "X1") (pin "RING_SW") (pinfunction "RING_SW_RING_SW") (pintype "bidirectional"))
      (node (ref "Y-MAX") (pin "1") (pinfunction "1_1") (pintype "passive"))
      (node (ref "Y-MIN") (pin "1") (pinfunction "1_1") (pintype "passive"))
    )
    (net (code "100") (name "Net-(A-MOT1-Pad1)") (class "Default")
      (node (ref "A-MOT1") (pin "1") (pinfunction "1_1") (pintype "bidirectional"))
      (node (ref "A-MOT2") (pin "1") (pinfunction "1_1") (pintype "passive"))
      (node (ref "U$1") (pin "2B") (pinfunction "2B_2B") (pintype "output"))
    )
    (net (code "101") (name "Net-(A-MOT1-Pad2)") (class "Default")
      (node (ref "A-MOT1") (pin "2") (pinfunction "2_2") (pintype "bidirectional"))
      (node (ref "A-MOT2") (pin "2") (pinfunction "2_2") (pintype "passive"))
      (node (ref "U$1") (pin "2A") (pinfunction "2A_2A") (pintype "output"))
    )
    (net (code "102") (name "Net-(A-MOT1-Pad3)") (class "Default")
      (node (ref "A-MOT1") (pin "3") (pinfunction "3_3") (pintype "bidirectional"))
      (node (ref "A-MOT2") (pin "3") (pinfunction "3_3") (pintype "passive"))
      (node (ref "U$1") (pin "1A") (pinfunction "1A_1A") (pintype "output"))
    )
    (net (code "103") (name "Net-(A-MOT1-Pad4)") (class "Default")
      (node (ref "A-MOT1") (pin "4") (pinfunction "4_4") (pintype "bidirectional"))
      (node (ref "A-MOT2") (pin "4") (pinfunction "4_4") (pintype "passive"))
      (node (ref "U$1") (pin "1B") (pinfunction "1B_1B") (pintype "output"))
    )
    (net (code "104") (name "Net-(A_STP-PadA)") (class "Default")
      (node (ref "A_STP") (pin "A") (pinfunction "A_A") (pintype "passive"))
      (node (ref "R6") (pin "1") (pinfunction "1_1") (pintype "passive"))
    )
    (net (code "105") (name "Net-(B-MOT1-Pad1)") (class "Default")
      (node (ref "B-MOT1") (pin "1") (pinfunction "1_1") (pintype "bidirectional"))
      (node (ref "B-MOT2") (pin "1") (pinfunction "1_1") (pintype "passive"))
      (node (ref "U$7") (pin "2B") (pinfunction "2B_2B") (pintype "output"))
    )
    (net (code "106") (name "Net-(B-MOT1-Pad2)") (class "Default")
      (node (ref "B-MOT1") (pin "2") (pinfunction "2_2") (pintype "bidirectional"))
      (node (ref "B-MOT2") (pin "2") (pinfunction "2_2") (pintype "passive"))
      (node (ref "U$7") (pin "2A") (pinfunction "2A_2A") (pintype "output"))
    )
    (net (code "107") (name "Net-(B-MOT1-Pad3)") (class "Default")
      (node (ref "B-MOT1") (pin "3") (pinfunction "3_3") (pintype "bidirectional"))
      (node (ref "B-MOT2") (pin "3") (pinfunction "3_3") (pintype "passive"))
      (node (ref "U$7") (pin "1A") (pinfunction "1A_1A") (pintype "output"))
    )
    (net (code "108") (name "Net-(B-MOT1-Pad4)") (class "Default")
      (node (ref "B-MOT1") (pin "4") (pinfunction "4_4") (pintype "bidirectional"))
      (node (ref "B-MOT2") (pin "4") (pinfunction "4_4") (pintype "passive"))
      (node (ref "U$7") (pin "1B") (pinfunction "1B_1B") (pintype "output"))
    )
    (net (code "109") (name "Net-(B_STP-PadA)") (class "Default")
      (node (ref "B_STP") (pin "A") (pinfunction "A_A") (pintype "passive"))
      (node (ref "R11") (pin "1") (pinfunction "1_1") (pintype "passive"))
    )
    (net (code "110") (name "Net-(C-MOT1-Pad1)") (class "Default")
      (node (ref "C-MOT1") (pin "1") (pinfunction "1_1") (pintype "bidirectional"))
      (node (ref "C-MOT2") (pin "1") (pinfunction "1_1") (pintype "passive"))
      (node (ref "U$6") (pin "2B") (pinfunction "2B_2B") (pintype "output"))
    )
    (net (code "111") (name "Net-(C-MOT1-Pad2)") (class "Default")
      (node (ref "C-MOT1") (pin "2") (pinfunction "2_2") (pintype "bidirectional"))
      (node (ref "C-MOT2") (pin "2") (pinfunction "2_2") (pintype "passive"))
      (node (ref "U$6") (pin "2A") (pinfunction "2A_2A") (pintype "output"))
    )
    (net (code "112") (name "Net-(C-MOT1-Pad3)") (class "Default")
      (node (ref "C-MOT1") (pin "3") (pinfunction "3_3") (pintype "bidirectional"))
      (node (ref "C-MOT2") (pin "3") (pinfunction "3_3") (pintype "passive"))
      (node (ref "U$6") (pin "1A") (pinfunction "1A_1A") (pintype "output"))
    )
    (net (code "113") (name "Net-(C-MOT1-Pad4)") (class "Default")
      (node (ref "C-MOT1") (pin "4") (pinfunction "4_4") (pintype "bidirectional"))
      (node (ref "C-MOT2") (pin "4") (pinfunction "4_4") (pintype "passive"))
      (node (ref "U$6") (pin "1B") (pinfunction "1B_1B") (pintype "output"))
    )
    (net (code "114") (name "Net-(C5-Pad1)") (class "Default")
      (node (ref "C5") (pin "1") (pinfunction "1_1") (pintype "passive"))
      (node (ref "IC1") (pin "COMP") (pinfunction "COMP_COMP") (pintype "bidirectional"))
    )
    (net (code "115") (name "Net-(C5-Pad2)") (class "Default")
      (node (ref "C5") (pin "2") (pinfunction "2_2") (pintype "passive"))
      (node (ref "R7") (pin "2") (pinfunction "2_2") (pintype "passive"))
    )
    (net (code "116") (name "Net-(C8-Pad1)") (class "Default")
      (node (ref "C8") (pin "1") (pinfunction "1_1") (pintype "passive"))
      (node (ref "IC1") (pin "BS") (pinfunction "BS_BS") (pintype "bidirectional"))
    )
    (net (code "117") (name "Net-(C8-Pad2)") (class "Default")
      (node (ref "C8") (pin "2") (pinfunction "2_2") (pintype "passive"))
      (node (ref "IC1") (pin "SW") (pinfunction "SW_SW") (pintype "bidirectional"))
      (node (ref "L1") (pin "1") (pinfunction "1_1") (pintype "passive"))
    )
    (net (code "118") (name "Net-(C9-Pad1)") (class "Default")
      (node (ref "C9") (pin "1") (pinfunction "1_1") (pintype "passive"))
      (node (ref "IC1") (pin "SS") (pinfunction "SS_SS") (pintype "bidirectional"))
    )
    (net (code "119") (name "Net-(C12-Pad+)") (class "Default")
      (node (ref "C12") (pin "+") (pinfunction "+_+") (pintype "passive"))
      (node (ref "C7") (pin "1") (pinfunction "1_1") (pintype "passive"))
      (node (ref "L1") (pin "2") (pinfunction "2_2") (pintype "passive"))
      (node (ref "ON_BOARD_PWR") (pin "2") (pinfunction "2_2") (pintype "passive"))
      (node (ref "R12") (pin "1") (pinfunction "1_1") (pintype "passive"))
      (node (ref "R9") (pin "2") (pinfunction "2_2") (pintype "passive"))
    )
    (net (code "120") (name "Net-(C_STP-PadA)") (class "Default")
      (node (ref "C_STP") (pin "A") (pinfunction "A_A") (pintype "passive"))
      (node (ref "R3") (pin "1") (pinfunction "1_1") (pintype "passive"))
    )
    (net (code "121") (name "Net-(D2-PadA)") (class "Default")
      (node (ref "D2") (pin "A") (pinfunction "A_A") (pintype "passive"))
      (node (ref "ON_BOARD_PWR") (pin "1") (pinfunction "1_1") (pintype "passive"))
    )
    (net (code "122") (name "Net-(D13-PadA)") (class "Default")
      (node (ref "D13") (pin "A") (pinfunction "A_A") (pintype "passive"))
      (node (ref "RN1") (pin "1") (pinfunction "1_1") (pintype "passive"))
    )
    (net (code "123") (name "Net-(IC1-PadEN)") (class "Default")
      (node (ref "IC1") (pin "EN") (pinfunction "EN_EN") (pintype "bidirectional"))
      (node (ref "R4") (pin "2") (pinfunction "2_2") (pintype "passive"))
    )
    (net (code "124") (name "Net-(IC1-PadFB)") (class "Default")
      (node (ref "IC1") (pin "FB") (pinfunction "FB_FB") (pintype "bidirectional"))
      (node (ref "R10") (pin "2") (pinfunction "2_2") (pintype "passive"))
      (node (ref "R9") (pin "1") (pinfunction "1_1") (pintype "passive"))
    )
    (net (code "125") (name "Net-(PWR1-PadA)") (class "Default")
      (node (ref "PWR1") (pin "A") (pinfunction "A_A") (pintype "passive"))
      (node (ref "R12") (pin "2") (pinfunction "2_2") (pintype "passive"))
    )
    (net (code "126") (name "Net-(R1-Pad1)") (class "Default")
      (node (ref "R1") (pin "1") (pinfunction "1_1") (pintype "passive"))
      (node (ref "SJ7") (pin "2") (pinfunction "2_2") (pintype "passive"))
      (node (ref "U$1") (pin "MS1") (pinfunction "MS1_MS1") (pintype "input"))
    )
    (net (code "127") (name "Net-(R5-Pad1)") (class "Default")
      (node (ref "R5") (pin "1") (pinfunction "1_1") (pintype "passive"))
      (node (ref "SJ1") (pin "2") (pinfunction "2_2") (pintype "passive"))
      (node (ref "U$6") (pin "MS1") (pinfunction "MS1_MS1") (pintype "input"))
    )
    (net (code "128") (name "Net-(R8-Pad1)") (class "Default")
      (node (ref "R8") (pin "1") (pinfunction "1_1") (pintype "passive"))
      (node (ref "SJ3") (pin "2") (pinfunction "2_2") (pintype "passive"))
      (node (ref "U$7") (pin "MS1") (pinfunction "MS1_MS1") (pintype "input"))
    )
    (net (code "129") (name "Net-(RN1B-1)") (class "Default")
      (node (ref "RN1") (pin "2") (pinfunction "1_2") (pintype "passive"))
      (node (ref "RX_LED") (pin "C") (pinfunction "C_C") (pintype "passive"))
    )
    (net (code "130") (name "Net-(RN1C-1)") (class "Default")
      (node (ref "RN1") (pin "3") (pinfunction "1_3") (pintype "passive"))
      (node (ref "TX_LED") (pin "C") (pinfunction "C_C") (pintype "passive"))
    )
    (net (code "131") (name "Net-(RN1D-1)") (class "Default")
      (node (ref "PWR") (pin "A") (pinfunction "A_A") (pintype "passive"))
      (node (ref "RN1") (pin "4") (pinfunction "1_4") (pintype "passive"))
    )
    (net (code "132") (name "Net-(SJ2-Pad2)") (class "Default")
      (node (ref "SJ2") (pin "2") (pinfunction "2_2") (pintype "passive"))
      (node (ref "U$6") (pin "MS2") (pinfunction "MS2_MS2") (pintype "input"))
    )
    (net (code "133") (name "Net-(SJ4-Pad2)") (class "Default")
      (node (ref "SJ4") (pin "2") (pinfunction "2_2") (pintype "passive"))
      (node (ref "U$7") (pin "MS2") (pinfunction "MS2_MS2") (pintype "input"))
    )
    (net (code "134") (name "Net-(SJ5-Pad2)") (class "Default")
      (node (ref "SJ5") (pin "2") (pinfunction "2_2") (pintype "passive"))
      (node (ref "U$6") (pin "MS3") (pinfunction "MS3_MS3") (pintype "input"))
    )
    (net (code "135") (name "Net-(SJ6-Pad2)") (class "Default")
      (node (ref "SJ6") (pin "2") (pinfunction "2_2") (pintype "passive"))
      (node (ref "U$7") (pin "MS3") (pinfunction "MS3_MS3") (pintype "input"))
    )
    (net (code "136") (name "Net-(SJ8-Pad2)") (class "Default")
      (node (ref "SJ8") (pin "2") (pinfunction "2_2") (pintype "passive"))
      (node (ref "U$1") (pin "MS2") (pinfunction "MS2_MS2") (pintype "input"))
    )
    (net (code "137") (name "Net-(SJ9-Pad2)") (class "Default")
      (node (ref "SJ9") (pin "2") (pinfunction "2_2") (pintype "passive"))
      (node (ref "U$1") (pin "MS3") (pinfunction "MS3_MS3") (pintype "input"))
    )
    (net (code "138") (name "Net-(U$1-SLEEP)") (class "Default")
      (node (ref "U$1") (pin "RST") (pinfunction "RST_RST") (pintype "input"))
      (node (ref "U$1") (pin "SLP") (pinfunction "SLEEP_SLP") (pintype "input"))
    )
    (net (code "139") (name "Net-(U$6-SLEEP)") (class "Default")
      (node (ref "U$6") (pin "RST") (pinfunction "RST_RST") (pintype "input"))
      (node (ref "U$6") (pin "SLP") (pinfunction "SLEEP_SLP") (pintype "input"))
    )
    (net (code "140") (name "Net-(U$7-SLEEP)") (class "Default")
      (node (ref "U$7") (pin "RST") (pinfunction "RST_RST") (pintype "input"))
      (node (ref "U$7") (pin "SLP") (pinfunction "SLEEP_SLP") (pintype "input"))
    )
    (net (code "141") (name "VCC") (class "Default")
      (node (ref "D2") (pin "C") (pinfunction "C_C") (pintype "passive"))
      (node (ref "IC5") (pin "20") (pinfunction "VCC_20") (pintype "power_in"))
      (node (ref "R18") (pin "1") (pinfunction "1_1") (pintype "passive"))
      (node (ref "R19") (pin "1") (pinfunction "1_1") (pintype "passive"))
      (node (ref "R2") (pin "1") (pinfunction "1_1") (pintype "passive"))
      (node (ref "RN1") (pin "5") (pinfunction "2_5") (pintype "passive"))
      (node (ref "RX_LED") (pin "A") (pinfunction "A_A") (pintype "passive"))
      (node (ref "SER1") (pin "2") (pinfunction "2_2") (pintype "passive"))
      (node (ref "SER2") (pin "2") (pinfunction "2_2") (pintype "passive"))
      (node (ref "SJ1") (pin "1") (pinfunction "1_1") (pintype "passive"))
      (node (ref "SJ2") (pin "1") (pinfunction "1_1") (pintype "passive"))
      (node (ref "SJ3") (pin "1") (pinfunction "1_1") (pintype "passive"))
      (node (ref "SJ4") (pin "1") (pinfunction "1_1") (pintype "passive"))
      (node (ref "SJ5") (pin "1") (pinfunction "1_1") (pintype "passive"))
      (node (ref "SJ6") (pin "1") (pinfunction "1_1") (pintype "passive"))
      (node (ref "SJ7") (pin "1") (pinfunction "1_1") (pintype "passive"))
      (node (ref "SJ8") (pin "1") (pinfunction "1_1") (pintype "passive"))
      (node (ref "SJ9") (pin "1") (pinfunction "1_1") (pintype "passive"))
      (node (ref "TFT") (pin "3") (pinfunction "3_3") (pintype "passive"))
      (node (ref "TX_LED") (pin "A") (pinfunction "A_A") (pintype "passive"))
      (node (ref "U$1") (pin "VDD") (pinfunction "VDD_VDD") (pintype "power_in"))
      (node (ref "U$6") (pin "VDD") (pinfunction "VDD_VDD") (pintype "power_in"))
      (node (ref "U$7") (pin "VDD") (pinfunction "VDD_VDD") (pintype "power_in"))
      (node (ref "U1") (pin "5V@0") (pinfunction "5V_5V@0") (pintype "power_in"))
      (node (ref "U1") (pin "5V@1") (pinfunction "5V_5V@1") (pintype "power_in"))
      (node (ref "U1") (pin "5V@2") (pinfunction "5V_5V@2") (pintype "power_in"))
      (node (ref "X-MAX") (pin "2") (pinfunction "2_2") (pintype "passive"))
      (node (ref "X-MIN") (pin "2") (pinfunction "2_2") (pintype "passive"))
      (node (ref "Y-MAX") (pin "2") (pinfunction "2_2") (pintype "passive"))
      (node (ref "Y-MIN") (pin "2") (pinfunction "2_2") (pintype "passive"))
    )
    (net (code "142") (name "unconnected-(D1-PadA)") (class "Default")
      (node (ref "D1") (pin "A") (pinfunction "A_A") (pintype "passive"))
    )
    (net (code "143") (name "unconnected-(D1-PadC)") (class "Default")
      (node (ref "D1") (pin "C") (pinfunction "C_C") (pintype "passive"))
    )
    (net (code "144") (name "unconnected-(IC3A-Y3-Pad16)") (class "Default")
      (node (ref "IC3") (pin "16") (pinfunction "Y3_16") (pintype "tri_state"))
    )
    (net (code "145") (name "unconnected-(IC3A-Y4-Pad15)") (class "Default")
      (node (ref "IC3") (pin "15") (pinfunction "Y4_15") (pintype "tri_state"))
    )
    (net (code "146") (name "unconnected-(IC3A-Y5-Pad14)") (class "Default")
      (node (ref "IC3") (pin "14") (pinfunction "Y5_14") (pintype "tri_state"))
    )
    (net (code "147") (name "unconnected-(IC3A-Y6-Pad13)") (class "Default")
      (node (ref "IC3") (pin "13") (pinfunction "Y6_13") (pintype "tri_state"))
    )
    (net (code "148") (name "unconnected-(IC3A-Y8-Pad11)") (class "Default")
      (node (ref "IC3") (pin "11") (pinfunction "Y8_11") (pintype "tri_state"))
    )
    (net (code "149") (name "unconnected-(IC4A-Y8-Pad11)") (class "Default")
      (node (ref "IC4") (pin "11") (pinfunction "Y8_11") (pintype "tri_state"))
    )
    (net (code "150") (name "unconnected-(IC5A-Y1-Pad18)") (class "Default")
      (node (ref "IC5") (pin "18") (pinfunction "Y1_18") (pintype "tri_state"))
    )
    (net (code "151") (name "unconnected-(IC5A-Y5-Pad14)") (class "Default")
      (node (ref "IC5") (pin "14") (pinfunction "Y5_14") (pintype "tri_state"))
    )
    (net (code "152") (name "unconnected-(IC5A-Y6-Pad13)") (class "Default")
      (node (ref "IC5") (pin "13") (pinfunction "Y6_13") (pintype "tri_state"))
    )
    (net (code "153") (name "unconnected-(IC5A-Y7-Pad12)") (class "Default")
      (node (ref "IC5") (pin "12") (pinfunction "Y7_12") (pintype "tri_state"))
    )
    (net (code "154") (name "unconnected-(IC5A-Y8-Pad11)") (class "Default")
      (node (ref "IC5") (pin "11") (pinfunction "Y8_11") (pintype "tri_state"))
    )
    (net (code "155") (name "unconnected-(TFT-Pad5)") (class "Default")
      (node (ref "TFT") (pin "5") (pinfunction "5_5") (pintype "passive"))
    )
    (net (code "156") (name "unconnected-(TFT-Pad24)") (class "Default")
      (node (ref "TFT") (pin "24") (pinfunction "24_24") (pintype "passive"))
    )
    (net (code "157") (name "unconnected-(TFT-Pad31)") (class "Default")
      (node (ref "TFT") (pin "31") (pinfunction "31_31") (pintype "passive"))
    )
    (net (code "158") (name "unconnected-(TFT-Pad35)") (class "Default")
      (node (ref "TFT") (pin "35") (pinfunction "35_35") (pintype "passive"))
    )
    (net (code "159") (name "unconnected-(TFT-Pad38)") (class "Default")
      (node (ref "TFT") (pin "38") (pinfunction "38_38") (pintype "passive"))
    )
    (net (code "160") (name "unconnected-(TFT-Pad39)") (class "Default")
      (node (ref "TFT") (pin "39") (pinfunction "39_39") (pintype "passive"))
    )
    (net (code "161") (name "unconnected-(TFT-Pad40)") (class "Default")
      (node (ref "TFT") (pin "40") (pinfunction "40_40") (pintype "passive"))
    )
  )
)
